# CAN.net
KiCad netlist of a schematic drawn in Altium Designer
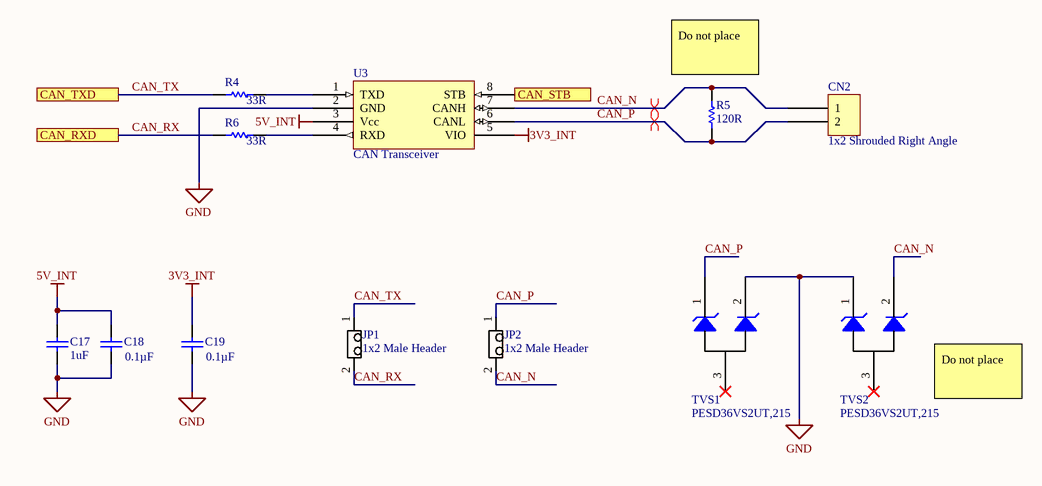
[diagram p0: CAN.SchDoc]

(export (version "E")
  (design (tool "Eeschema 10.0.6"))
  (components
    (comp (ref "C17")
      (value "CL21B105KBFNNNG")
      (footprint "0803 CAP")
      (description "SAMSUNG ELECTRO-MECHANICS - CL21B105KBFNNNG - MLCC CAPACITORS")
      (fields
        (field (name "TOLERANCE") "10%")
        (field (name "CAPACITANCE") "1uF")
        (field (name "VOLTAGE") "50V")
      )
      (libsource (lib "") (part "Symbol_1"))
    )
    (comp (ref "C18")
      (value "0.1µF")
      (footprint "CAPC2012N(0805\")")
      (description "Capacitor, Ceramic, 50V, +/-5%, 0805 SMD, X7R")
      (fields (field (name "Comment") "0.1uF 50V 0805 SMD, Ceramic") (field (name "PUBLISHER") "AUVic"))
      (libsource (lib "AUVIC") (part "Symbol"))
    )
    (comp (ref "C19")
      (value "0.1µF")
      (footprint "CAPC2012N(0805\")")
      (description "Capacitor, Ceramic, 50V, +/-5%, 0805 SMD, X7R")
      (fields (field (name "Comment") "0.1uF 50V 0805 SMD, Ceramic") (field (name "PUBLISHER") "AUVic"))
      (libsource (lib "AUVIC") (part "Symbol"))
    )
    (comp (ref "CN2")
      (value "1x2 Shrouded Right Angle")
      (footprint "2X1 Female Header")
      (description "02 MTE HDR SRRA LATCH")
      (libsource (lib "AUVIC") (part "1x2 Shrouded Right Angle"))
    )
    (comp (ref "JP1")
      (value "1x2 Male Header")
      (footprint "2X1 Males Header")
      (fields (field (name "MADE BY") "Andy Bates"))
      (libsource (lib "AUVIC") (part "1x2 Male Header"))
    )
    (comp (ref "JP2")
      (value "1x2 Male Header")
      (footprint "2X1 Males Header")
      (fields (field (name "MADE BY") "Andy Bates"))
      (libsource (lib "AUVIC") (part "1x2 Male Header"))
    )
    (comp (ref "R4")
      (value "33R")
      (footprint "RESC1608X55X25LL10T15")
      (description "Res Thick Film 0603 33 Ohm 1% 1/10W +/-100ppm/ßC Molded SMD Paper T/R")
      (fields (field (name "TOLERANCE") "1%"))
      (libsource (lib "AUVIC") (part "RES-2"))
    )
    (comp (ref "R5")
      (value "120R")
      (footprint "RESC1608X55X25LL10T15")
      (description "Res Thick Film 0603 120 Ohm 1% 0.1W(1/10W) ±100ppm/C Epoxy SMD T/R")
      (fields (field (name "TOLERANCE") "1%"))
      (libsource (lib "AUVIC") (part "RES-2"))
    )
    (comp (ref "R6")
      (value "33R")
      (footprint "RESC1608X55X25LL10T15")
      (description "Res Thick Film 0603 33 Ohm 1% 1/10W +/-100ppm/ßC Molded SMD Paper T/R")
      (fields (field (name "TOLERANCE") "1%"))
      (libsource (lib "AUVIC") (part "RES-2"))
    )
    (comp (ref "TVS1")
      (value "PESD36VS2UT,215")
      (footprint "SOT95P245X110-3N")
      (description "TVS DIODE 36V 60V SOT23")
      (fields (field (name "CREATED BY") "Miguel Manguerra"))
      (libsource (lib "AUVIC") (part "PESD36VS2UT,215"))
    )
    (comp (ref "TVS2")
      (value "PESD36VS2UT,215")
      (footprint "SOT95P245X110-3N")
      (description "TVS DIODE 36V 60V SOT23")
      (fields (field (name "CREATED BY") "Miguel Manguerra"))
      (libsource (lib "AUVIC") (part "PESD36VS2UT,215"))
    )
    (comp (ref "U3")
      (value "CAN Transceiver")
      (footprint "8-SOIC")
      (description "1/1 Transceiver Half CANbus 8-SO")
      (libsource (lib "AUVIC") (part "CAN Transceiver"))
    )
  )
  (nets
    (net (code "1") (name "/CAN_N") (class "Default")
      (node (ref "CN2") (pin "1") (pinfunction "1_1") (pintype "passive"))
      (node (ref "JP2") (pin "2") (pinfunction "2_2") (pintype "passive"))
      (node (ref "R5") (pin "2") (pinfunction "2_2") (pintype "passive"))
      (node (ref "TVS2") (pin "2") (pinfunction "Cathode_2_2") (pintype "passive"))
      (node (ref "U3") (pin "7") (pinfunction "CANH_7") (pintype "bidirectional"))
    )
    (net (code "2") (name "/CAN_P") (class "Default")
      (node (ref "CN2") (pin "2") (pinfunction "2_2") (pintype "passive"))
      (node (ref "JP2") (pin "1") (pinfunction "1_1") (pintype "passive"))
      (node (ref "R5") (pin "1") (pinfunction "1_1") (pintype "passive"))
      (node (ref "TVS1") (pin "1") (pinfunction "Cathode_1_1") (pintype "passive"))
      (node (ref "U3") (pin "6") (pinfunction "CANL_6") (pintype "bidirectional"))
    )
    (net (code "3") (name "/CAN_RX") (class "Default")
      (node (ref "JP1") (pin "2") (pinfunction "2_2") (pintype "passive"))
      (node (ref "R6") (pin "1") (pinfunction "1_1") (pintype "passive"))
    )
    (net (code "4") (name "/CAN_STB") (class "Default")
      (node (ref "U3") (pin "8") (pinfunction "STB_8") (pintype "input"))
    )
    (net (code "5") (name "/CAN_TX") (class "Default")
      (node (ref "JP1") (pin "1") (pinfunction "1_1") (pintype "passive"))
      (node (ref "R4") (pin "1") (pinfunction "1_1") (pintype "passive"))
    )
    (net (code "6") (name "3V3_INT") (class "Default")
      (node (ref "C19") (pin "2") (pinfunction "Cathode_2") (pintype "passive"))
      (node (ref "U3") (pin "5") (pinfunction "VIO_5") (pintype "passive"))
    )
    (net (code "7") (name "5V_INT") (class "Default")
      (node (ref "C17") (pin "2") (pinfunction "2_2") (pintype "passive"))
      (node (ref "C18") (pin "2") (pinfunction "Cathode_2") (pintype "passive"))
      (node (ref "U3") (pin "3") (pinfunction "Vcc_3") (pintype "power_in"))
    )
    (net (code "8") (name "GND") (class "Default")
      (node (ref "C17") (pin "1") (pinfunction "1_1") (pintype "passive"))
      (node (ref "C18") (pin "1") (pinfunction "Anode_1") (pintype "passive"))
      (node (ref "C19") (pin "1") (pinfunction "Anode_1") (pintype "passive"))
      (node (ref "TVS1") (pin "2") (pinfunction "Cathode_2_2") (pintype "passive"))
      (node (ref "TVS2") (pin "1") (pinfunction "Cathode_1_1") (pintype "passive"))
      (node (ref "U3") (pin "2") (pinfunction "GND_2") (pintype "power_in"))
    )
    (net (code "9") (name "Net-(U3-RXD)") (class "Default")
      (node (ref "R6") (pin "2") (pinfunction "2_2") (pintype "passive"))
      (node (ref "U3") (pin "4") (pinfunction "RXD_4") (pintype "output"))
    )
    (net (code "10") (name "Net-(U3-TXD)") (class "Default")
      (node (ref "R4") (pin "2") (pinfunction "2_2") (pintype "passive"))
      (node (ref "U3") (pin "1") (pinfunction "TXD_1") (pintype "input"))
    )
    (net (code "11") (name "unconnected-(TVS1-Common_Anode-Pad3)") (class "Default")
      (node (ref "TVS1") (pin "3") (pinfunction "Common_Anode_3") (pintype "passive"))
    )
    (net (code "12") (name "unconnected-(TVS2-Common_Anode-Pad3)") (class "Default")
      (node (ref "TVS2") (pin "3") (pinfunction "Common_Anode_3") (pintype "passive"))
    )
  )
)
